# DAC.net
KiCad netlist of a schematic drawn in EAGLE
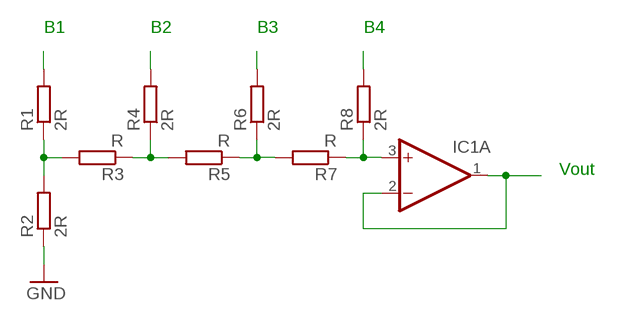
[diagram p0: schematic, sheet 1]

(export (version "E")
  (design (tool "Eeschema 10.0.6"))
  (components
    (comp (ref "IC1")
      (value "QUAD_OPAMPP")
      (footprint "eagle-import:DIL14")
      (libsource (lib "eagle-import") (part "QUAD_OPAMPP"))
    )
    (comp (ref "R1")
      (value "2R")
      (footprint "eagle-import:0309_12")
      (libsource (lib "eagle-import") (part "R-EU_0309/12"))
    )
    (comp (ref "R2")
      (value "2R")
      (footprint "eagle-import:0309_12")
      (libsource (lib "eagle-import") (part "R-EU_0309/12"))
    )
    (comp (ref "R3")
      (value "R")
      (footprint "eagle-import:0309_12")
      (libsource (lib "eagle-import") (part "R-EU_0309/12"))
    )
    (comp (ref "R4")
      (value "2R")
      (footprint "eagle-import:0309_12")
      (libsource (lib "eagle-import") (part "R-EU_0309/12"))
    )
    (comp (ref "R5")
      (value "R")
      (footprint "eagle-import:0309_12")
      (libsource (lib "eagle-import") (part "R-EU_0309/12"))
    )
    (comp (ref "R6")
      (value "2R")
      (footprint "eagle-import:0309_12")
      (libsource (lib "eagle-import") (part "R-EU_0309/12"))
    )
    (comp (ref "R7")
      (value "R")
      (footprint "eagle-import:0309_12")
      (libsource (lib "eagle-import") (part "R-EU_0309/12"))
    )
    (comp (ref "R8")
      (value "2R")
      (footprint "eagle-import:0309_12")
      (libsource (lib "eagle-import") (part "R-EU_0309/12"))
    )
  )
  (nets
    (net (code "1") (name "GND") (class "Default")
      (node (ref "R2") (pin "1") (pinfunction "1_1") (pintype "passive"))
    )
    (net (code "2") (name "Net-(IC1A-+IN)") (class "Default")
      (node (ref "IC1") (pin "3") (pinfunction "+IN_3") (pintype "input"))
      (node (ref "R7") (pin "1") (pinfunction "1_1") (pintype "passive"))
      (node (ref "R8") (pin "1") (pinfunction "1_1") (pintype "passive"))
    )
    (net (code "3") (name "Net-(IC1A--IN)") (class "Default")
      (node (ref "IC1") (pin "1") (pinfunction "OUT_1") (pintype "output"))
      (node (ref "IC1") (pin "2") (pinfunction "-IN_2") (pintype "input"))
    )
    (net (code "4") (name "Net-(R1-Pad1)") (class "Default")
      (node (ref "R1") (pin "1") (pinfunction "1_1") (pintype "passive"))
      (node (ref "R2") (pin "2") (pinfunction "2_2") (pintype "passive"))
      (node (ref "R3") (pin "2") (pinfunction "2_2") (pintype "passive"))
    )
    (net (code "5") (name "Net-(R3-Pad1)") (class "Default")
      (node (ref "R3") (pin "1") (pinfunction "1_1") (pintype "passive"))
      (node (ref "R4") (pin "1") (pinfunction "1_1") (pintype "passive"))
      (node (ref "R5") (pin "2") (pinfunction "2_2") (pintype "passive"))
    )
    (net (code "6") (name "Net-(R5-Pad1)") (class "Default")
      (node (ref "R5") (pin "1") (pinfunction "1_1") (pintype "passive"))
      (node (ref "R6") (pin "1") (pinfunction "1_1") (pintype "passive"))
      (node (ref "R7") (pin "2") (pinfunction "2_2") (pintype "passive"))
    )
    (net (code "7") (name "unconnected-(R1-Pad2)") (class "Default")
      (node (ref "R1") (pin "2") (pinfunction "2_2") (pintype "passive"))
    )
    (net (code "8") (name "unconnected-(R4-Pad2)") (class "Default")
      (node (ref "R4") (pin "2") (pinfunction "2_2") (pintype "passive"))
    )
    (net (code "9") (name "unconnected-(R6-Pad2)") (class "Default")
      (node (ref "R6") (pin "2") (pinfunction "2_2") (pintype "passive"))
    )
    (net (code "10") (name "unconnected-(R8-Pad2)") (class "Default")
      (node (ref "R8") (pin "2") (pinfunction "2_2") (pintype "passive"))
    )
  )
)
